# Chov2_cpu.net
KiCad netlist of a schematic drawn in Altium Designer
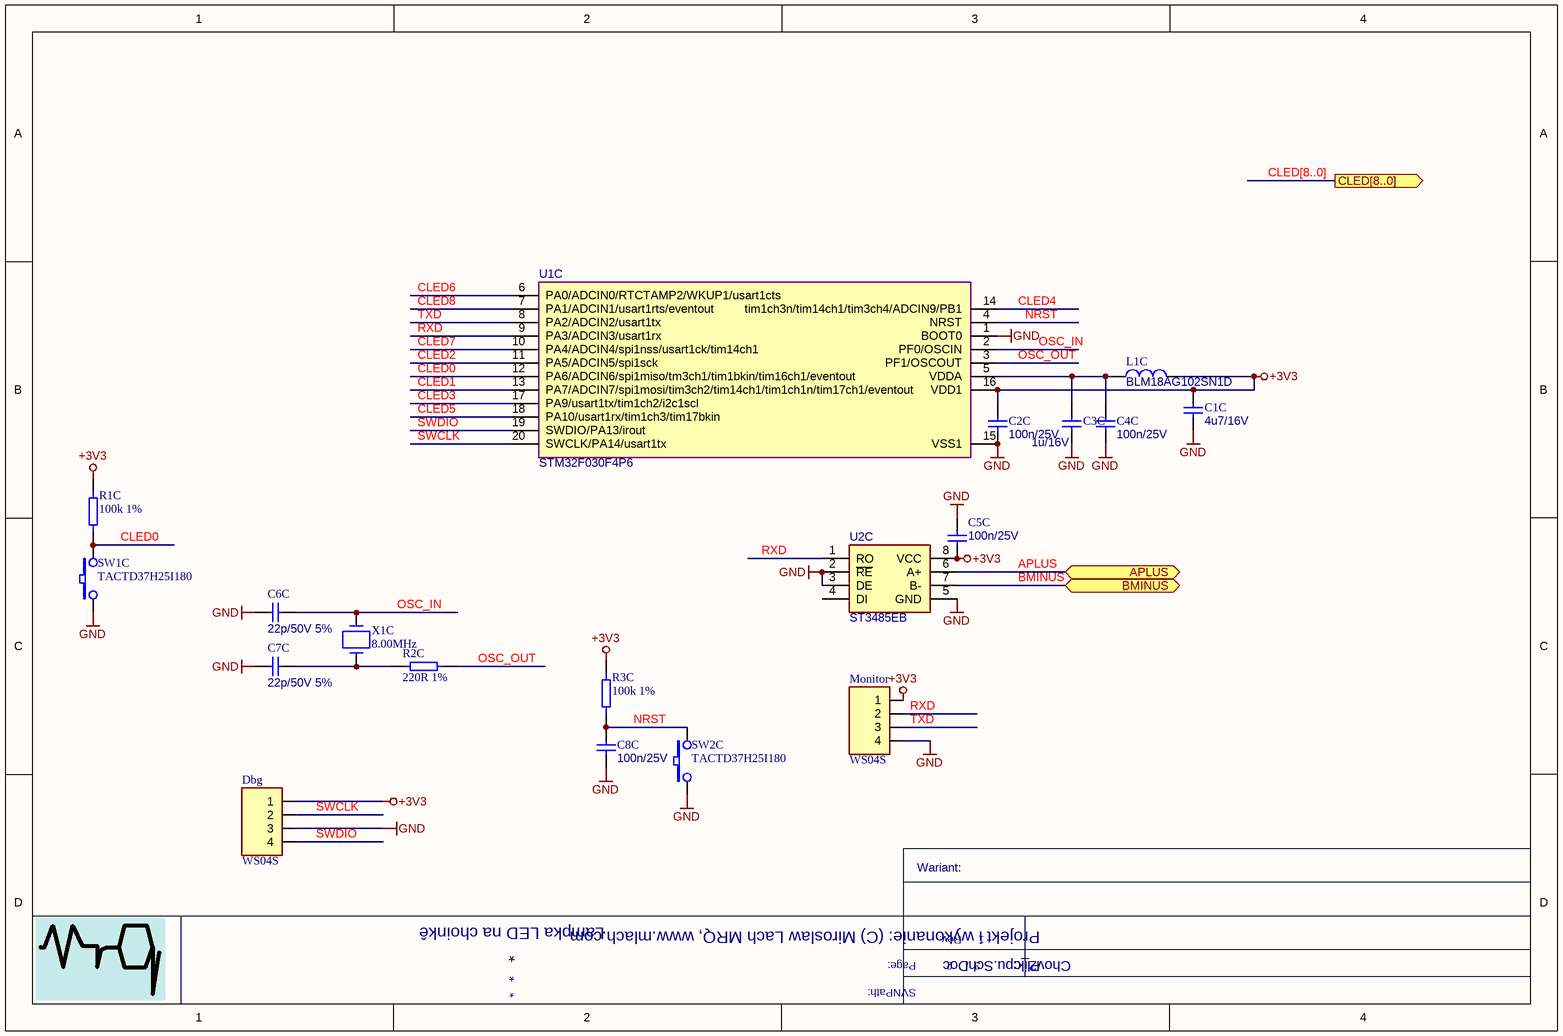
[diagram p0: Chov2_cpu.SchDoc]

(export (version "E")
  (design (tool "Eeschema 10.0.6"))
  (components
    (comp (ref "C1C")
      (value "0805YC475KAT2A")
      (footprint "0805")
      (fields (field (name "OTHERPARAMS") "4u7/16V") (field (name "TOLERANCE") "10%"))
      (libsource (lib "Parts") (part "C"))
    )
    (comp (ref "C2C")
      (value "CL10B104KA8NNNC")
      (footprint "0603-IPC")
      (fields (field (name "OTHERPARAMS") "100n/25V") (field (name "TOLERANCE") "10%"))
      (libsource (lib "Parts") (part "C"))
    )
    (comp (ref "C3C")
      (value "CL10B105KO8NNNC")
      (footprint "0603-IPC")
      (fields (field (name "OTHERPARAMS") "1u/16V") (field (name "TOLERANCE") "10%"))
      (libsource (lib "Parts") (part "C"))
    )
    (comp (ref "C4C")
      (value "CL10B104KA8NNNC")
      (footprint "0603-IPC")
      (fields (field (name "OTHERPARAMS") "100n/25V") (field (name "TOLERANCE") "10%"))
      (libsource (lib "Parts") (part "C"))
    )
    (comp (ref "C5C")
      (value "CL10B104KA8NNNC")
      (footprint "0603-IPC")
      (fields (field (name "OTHERPARAMS") "100n/25V") (field (name "TOLERANCE") "10%"))
      (libsource (lib "Parts") (part "C"))
    )
    (comp (ref "C6C")
      (value "CL10C220JB8NNNC")
      (footprint "0603-IPC")
      (fields (field (name "OTHERPARAMS") "22p/50V 5%") (field (name "TOLERANCE") "5%"))
      (libsource (lib "Parts") (part "C"))
    )
    (comp (ref "C7C")
      (value "CL10C220JB8NNNC")
      (footprint "0603-IPC")
      (fields (field (name "OTHERPARAMS") "22p/50V 5%") (field (name "TOLERANCE") "5%"))
      (libsource (lib "Parts") (part "C"))
    )
    (comp (ref "C8C")
      (value "CL10B104KA8NNNC")
      (footprint "0603-IPC")
      (fields (field (name "OTHERPARAMS") "100n/25V") (field (name "TOLERANCE") "10%"))
      (libsource (lib "Parts") (part "C"))
    )
    (comp (ref "Dbg") (value "WS04S") (footprint "WS04S") (libsource (lib "Parts") (part "HEADER4")))
    (comp (ref "L1C")
      (value "BLM18AG102SN1D")
      (footprint "0603")
      (fields (field (name "OTHERPARAMS") "BLM18AG102SN1D"))
      (libsource (lib "Parts") (part "INDUCTOR"))
    )
    (comp (ref "Monitor") (value "WS04S") (footprint "WS04S") (libsource (lib "Parts") (part "HEADER4")))
    (comp (ref "R1C")
      (value "RC0603FR-07100KL")
      (footprint "0603-IPC")
      (fields (field (name "OTHERPARAMS") "100k 1%") (field (name "TOLERANCE") "1%"))
      (libsource (lib "Parts") (part "R"))
    )
    (comp (ref "R2C")
      (value "0603SAF2200T5E")
      (footprint "0603-IPC")
      (fields (field (name "OTHERPARAMS") "220R 1%") (field (name "TOLERANCE") "1%"))
      (libsource (lib "Parts") (part "R"))
    )
    (comp (ref "R3C")
      (value "RC0603FR-07100KL")
      (footprint "0603-IPC")
      (fields (field (name "OTHERPARAMS") "100k 1%") (field (name "TOLERANCE") "1%"))
      (libsource (lib "Parts") (part "R"))
    )
    (comp (ref "SW1C")
      (value "TACTD37H25I180")
      (footprint "TACTD37H25I180")
      (libsource (lib "Parts") (part "DTSM31NB"))
    )
    (comp (ref "SW2C")
      (value "TACTD37H25I180")
      (footprint "TACTD37H25I180")
      (libsource (lib "Parts") (part "DTSM31NB"))
    )
    (comp (ref "U1C")
      (value "STM32F030F4P6")
      (footprint "MO-153AC")
      (libsource (lib "Parts") (part "STM32F030F4P6"))
    )
    (comp (ref "U2C") (value "ST3485EB") (footprint "8SOIC150") (libsource (lib "Parts") (part "SP3072")))
    (comp (ref "X1C") (value "8.00MHz") (footprint "HC49SMP") (libsource (lib "Parts") (part "CRYSTAL")))
  )
  (nets
    (net (code "1") (name "+3V3") (class "Default")
      (node (ref "C1C") (pin "1") (pinfunction "1_1") (pintype "passive"))
      (node (ref "C2C") (pin "1") (pinfunction "1_1") (pintype "passive"))
      (node (ref "C5C") (pin "1") (pinfunction "1_1") (pintype "passive"))
      (node (ref "Dbg") (pin "1") (pinfunction "1_1") (pintype "passive"))
      (node (ref "L1C") (pin "2") (pinfunction "2_2") (pintype "passive"))
      (node (ref "Monitor") (pin "1") (pinfunction "1_1") (pintype "passive"))
      (node (ref "R1C") (pin "1") (pinfunction "1_1") (pintype "passive"))
      (node (ref "R3C") (pin "1") (pinfunction "1_1") (pintype "passive"))
      (node (ref "U1C") (pin "16") (pinfunction "VDD1_16") (pintype "passive"))
      (node (ref "U2C") (pin "8") (pinfunction "VCC_8") (pintype "passive"))
    )
    (net (code "2") (name "/APLUS") (class "Default")
      (node (ref "U2C") (pin "6") (pinfunction "A+_6") (pintype "passive"))
    )
    (net (code "3") (name "/BMINUS") (class "Default")
      (node (ref "U2C") (pin "7") (pinfunction "B-_7") (pintype "passive"))
    )
    (net (code "4") (name "/CLED0") (class "Default")
      (node (ref "R1C") (pin "2") (pinfunction "2_2") (pintype "passive"))
      (node (ref "SW1C") (pin "2") (pinfunction "2_2") (pintype "passive"))
      (node (ref "U1C") (pin "12") (pinfunction "PA6/ADCIN6/spi1miso/tm3ch1/tim1bkin/tim16ch1/eventout_12") (pintype "passive"))
    )
    (net (code "5") (name "/CLED1") (class "Default")
      (node (ref "U1C") (pin "13") (pinfunction "PA7/ADCIN7/spi1mosi/tim3ch2/tim14ch1/tim1ch1n/tim17ch1/eventout_13") (pintype "passive"))
    )
    (net (code "6") (name "/CLED2") (class "Default")
      (node (ref "U1C") (pin "11") (pinfunction "PA5/ADCIN5/spi1sck_11") (pintype "passive"))
    )
    (net (code "7") (name "/CLED3") (class "Default")
      (node (ref "U1C") (pin "17") (pinfunction "PA9/usart1tx/tim1ch2/i2c1scl_17") (pintype "passive"))
    )
    (net (code "8") (name "/CLED4") (class "Default")
      (node (ref "U1C") (pin "14") (pinfunction "tim1ch3n/tim14ch1/tim3ch4/ADCIN9/PB1_14") (pintype "passive"))
    )
    (net (code "9") (name "/CLED5") (class "Default")
      (node (ref "U1C") (pin "18") (pinfunction "PA10/usart1rx/tim1ch3/tim17bkin_18") (pintype "passive"))
    )
    (net (code "10") (name "/CLED6") (class "Default")
      (node (ref "U1C") (pin "6") (pinfunction "PA0/ADCIN0/RTCTAMP2/WKUP1/usart1cts_6") (pintype "passive"))
    )
    (net (code "11") (name "/CLED7") (class "Default")
      (node (ref "U1C") (pin "10") (pinfunction "PA4/ADCIN4/spi1nss/usart1ck/tim14ch1_10") (pintype "passive"))
    )
    (net (code "12") (name "/CLED8") (class "Default")
      (node (ref "U1C") (pin "7") (pinfunction "PA1/ADCIN1/usart1rts/eventout_7") (pintype "passive"))
    )
    (net (code "14") (name "/NRST") (class "Default")
      (node (ref "C8C") (pin "1") (pinfunction "1_1") (pintype "passive"))
      (node (ref "R3C") (pin "2") (pinfunction "2_2") (pintype "passive"))
      (node (ref "SW2C") (pin "2") (pinfunction "2_2") (pintype "passive"))
      (node (ref "U1C") (pin "4") (pinfunction "NRST_4") (pintype "passive"))
    )
    (net (code "15") (name "/OSC_IN") (class "Default")
      (node (ref "C6C") (pin "2") (pinfunction "2_2") (pintype "passive"))
      (node (ref "U1C") (pin "2") (pinfunction "PF0/OSCIN_2") (pintype "passive"))
      (node (ref "X1C") (pin "1") (pinfunction "1_1") (pintype "passive"))
    )
    (net (code "16") (name "/OSC_OUT") (class "Default")
      (node (ref "R2C") (pin "2") (pinfunction "2_2") (pintype "passive"))
      (node (ref "U1C") (pin "3") (pinfunction "PF1/OSCOUT_3") (pintype "passive"))
    )
    (net (code "17") (name "/RXD") (class "Default")
      (node (ref "Monitor") (pin "2") (pinfunction "2_2") (pintype "passive"))
      (node (ref "U1C") (pin "9") (pinfunction "PA3/ADCIN3/usart1rx_9") (pintype "passive"))
      (node (ref "U2C") (pin "1") (pinfunction "RO_1") (pintype "passive"))
    )
    (net (code "18") (name "/SWCLK") (class "Default")
      (node (ref "Dbg") (pin "2") (pinfunction "2_2") (pintype "passive"))
      (node (ref "U1C") (pin "20") (pinfunction "SWCLK/PA14/usart1tx_20") (pintype "passive"))
    )
    (net (code "19") (name "/SWDIO") (class "Default")
      (node (ref "Dbg") (pin "4") (pinfunction "4_4") (pintype "passive"))
      (node (ref "U1C") (pin "19") (pinfunction "SWDIO/PA13/irout_19") (pintype "passive"))
    )
    (net (code "20") (name "/TXD") (class "Default")
      (node (ref "Monitor") (pin "3") (pinfunction "3_3") (pintype "passive"))
      (node (ref "U1C") (pin "8") (pinfunction "PA2/ADCIN2/usart1tx_8") (pintype "passive"))
    )
    (net (code "21") (name "GND") (class "Default")
      (node (ref "C1C") (pin "2") (pinfunction "2_2") (pintype "passive"))
      (node (ref "C2C") (pin "2") (pinfunction "2_2") (pintype "passive"))
      (node (ref "C3C") (pin "2") (pinfunction "2_2") (pintype "passive"))
      (node (ref "C4C") (pin "2") (pinfunction "2_2") (pintype "passive"))
      (node (ref "C5C") (pin "2") (pinfunction "2_2") (pintype "passive"))
      (node (ref "C6C") (pin "1") (pinfunction "1_1") (pintype "passive"))
      (node (ref "C7C") (pin "1") (pinfunction "1_1") (pintype "passive"))
      (node (ref "C8C") (pin "2") (pinfunction "2_2") (pintype "passive"))
      (node (ref "Dbg") (pin "3") (pinfunction "3_3") (pintype "passive"))
      (node (ref "Monitor") (pin "4") (pinfunction "4_4") (pintype "passive"))
      (node (ref "SW1C") (pin "1") (pinfunction "1_1") (pintype "passive"))
      (node (ref "SW2C") (pin "1") (pinfunction "1_1") (pintype "passive"))
      (node (ref "U1C") (pin "1") (pinfunction "BOOT0_1") (pintype "passive"))
      (node (ref "U1C") (pin "15") (pinfunction "VSS1_15") (pintype "passive"))
      (node (ref "U2C") (pin "2") (pinfunction "~{RE}_2") (pintype "passive"))
      (node (ref "U2C") (pin "3") (pinfunction "DE_3") (pintype "passive"))
      (node (ref "U2C") (pin "5") (pinfunction "GND_5") (pintype "passive"))
    )
    (net (code "22") (name "Net-(C7C-Pad2)") (class "Default")
      (node (ref "C7C") (pin "2") (pinfunction "2_2") (pintype "passive"))
      (node (ref "R2C") (pin "1") (pinfunction "1_1") (pintype "passive"))
      (node (ref "X1C") (pin "2") (pinfunction "2_2") (pintype "passive"))
    )
    (net (code "23") (name "Net-(U1C-VDDA)") (class "Default")
      (node (ref "C3C") (pin "1") (pinfunction "1_1") (pintype "passive"))
      (node (ref "C4C") (pin "1") (pinfunction "1_1") (pintype "passive"))
      (node (ref "L1C") (pin "1") (pinfunction "1_1") (pintype "passive"))
      (node (ref "U1C") (pin "5") (pinfunction "VDDA_5") (pintype "passive"))
    )
    (net (code "24") (name "unconnected-(U2C-DI-Pad4)") (class "Default")
      (node (ref "U2C") (pin "4") (pinfunction "DI_4") (pintype "passive"))
    )
  )
)
